# POWER_VOLTAGE.net
KiCad netlist of a schematic drawn in Altium Designer
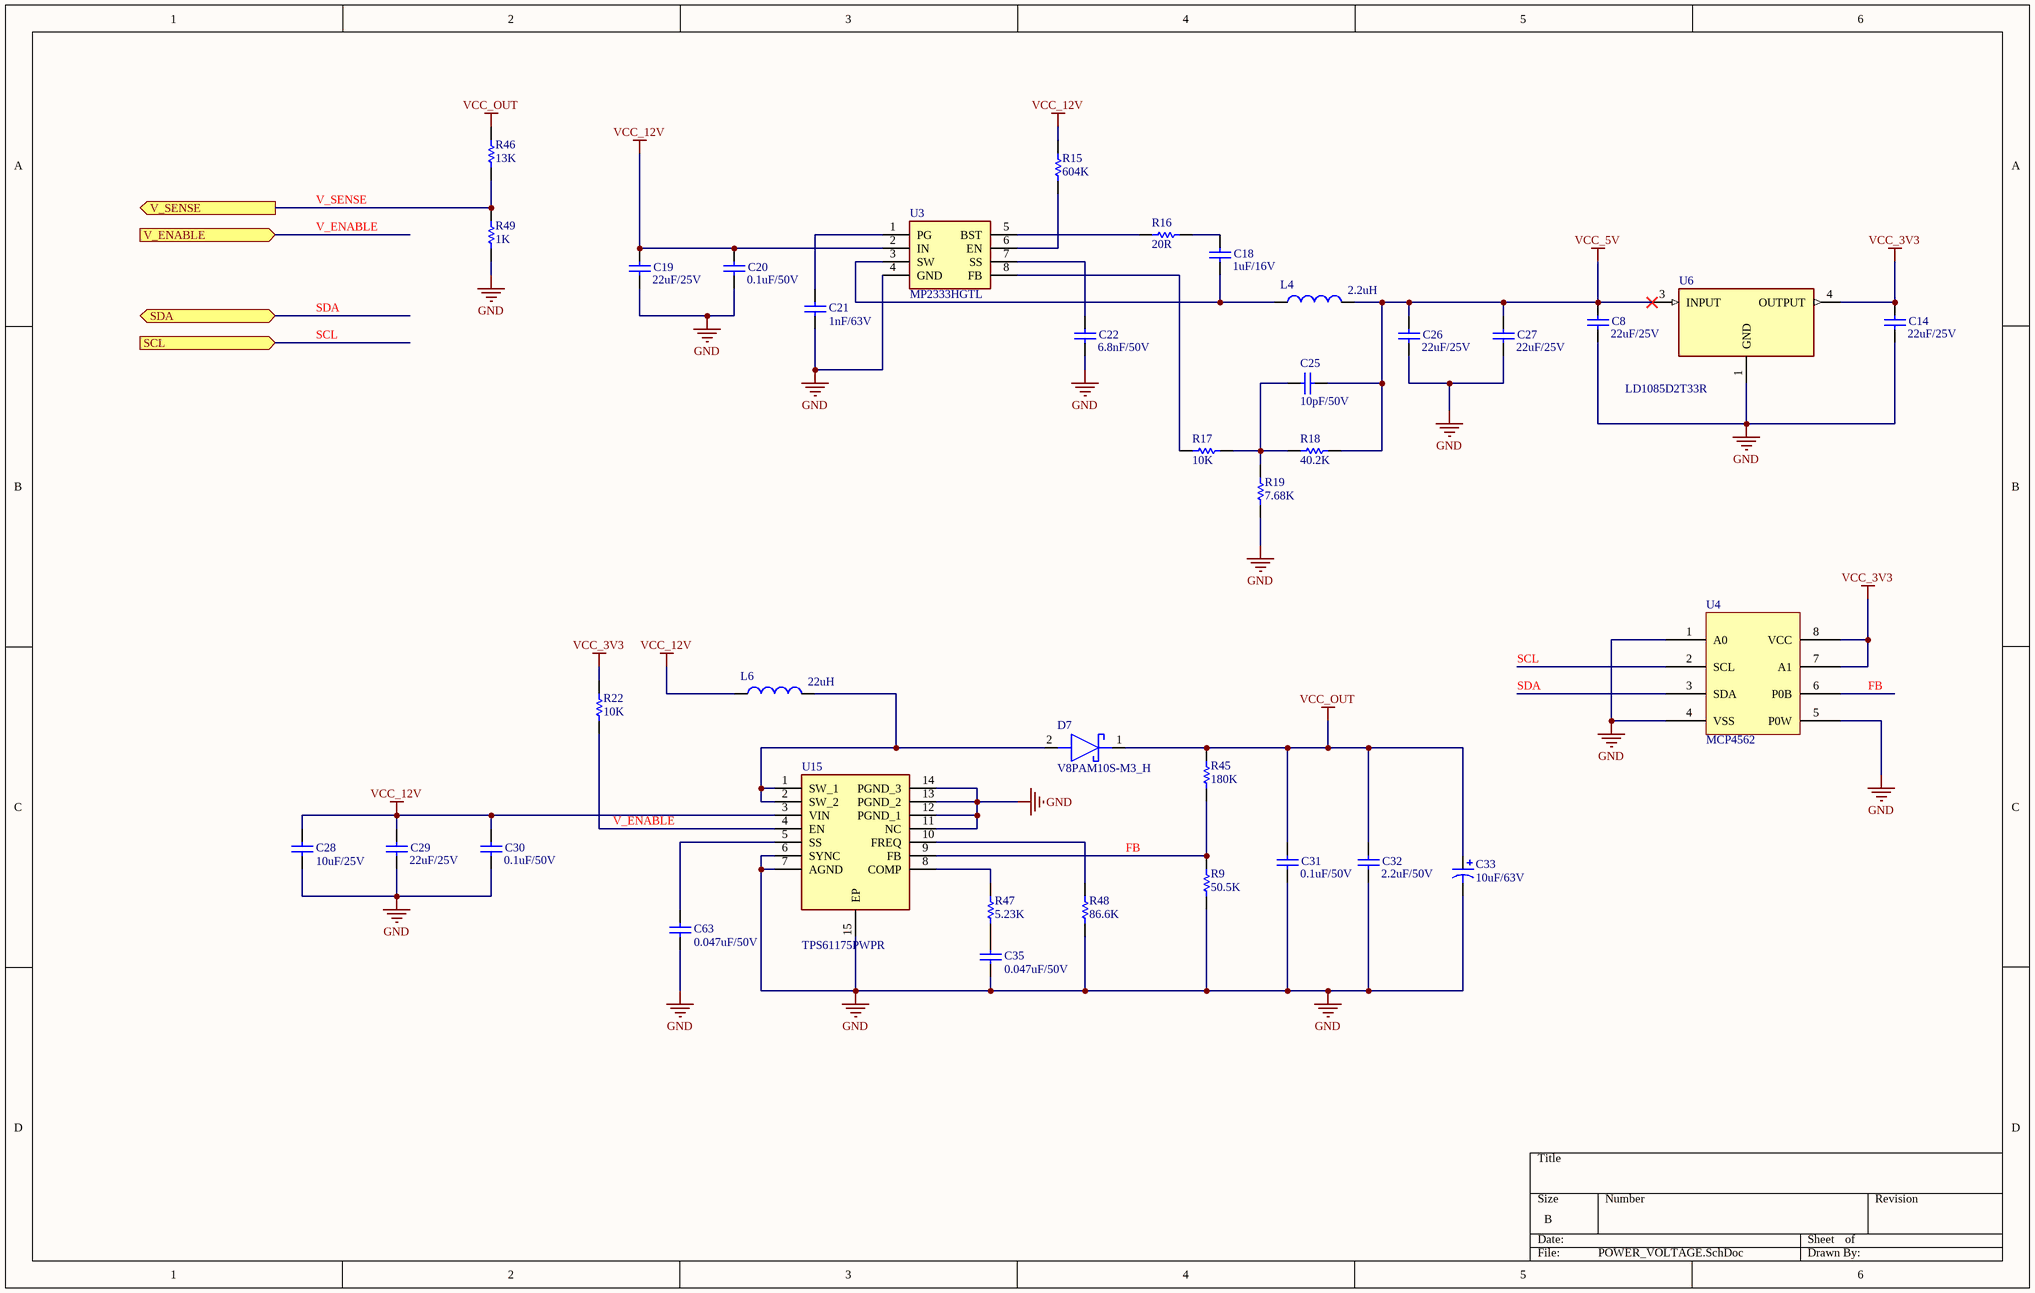
[diagram p0: POWER_VOLTAGE.SchDoc]

(export (version "E")
  (design (tool "Eeschema 10.0.6"))
  (components
    (comp (ref "C8")
      (value "22uF/25V")
      (footprint "1210C")
      (description "Multilayer Ceramic Capacitors MLCC - SMD/SMT 1210 25VDC 22uF 20% X7R AEC-Q200")
      (fields (field (name "MFR") "Taiyo Yuden") (field (name "MFR PART NO") "TMK325B7226MMHP"))
      (libsource (lib "Miscellaneous Devices") (part "Cap"))
    )
    (comp (ref "C14")
      (value "22uF/25V")
      (footprint "1210C")
      (description "Multilayer Ceramic Capacitors MLCC - SMD/SMT 1210 25VDC 22uF 20% X7R AEC-Q200")
      (fields (field (name "MFR") "Taiyo Yuden") (field (name "MFR PART NO") "TMK325B7226MMHP"))
      (libsource (lib "Miscellaneous Devices") (part "Cap"))
    )
    (comp (ref "C18")
      (value "1uF/16V")
      (footprint "0603C")
      (description "Multilayer Ceramic Capacitors MLCC - SMD/SMT 16volts 1uF X7R 10%")
      (fields (field (name "MFR") "KEMET") (field (name "MFR PART NO") "C0603C105K4RAC7411"))
      (libsource (lib "Miscellaneous Devices") (part "Cap"))
    )
    (comp (ref "C19")
      (value "22uF/25V")
      (footprint "1210C")
      (description "Multilayer Ceramic Capacitors MLCC - SMD/SMT 1210 25VDC 22uF 20% X7R AEC-Q200")
      (fields (field (name "MFR") "Taiyo Yuden") (field (name "MFR PART NO") "TMK325B7226MMHP"))
      (libsource (lib "Miscellaneous Devices") (part "Cap"))
    )
    (comp (ref "C20")
      (value "0.1uF/50V")
      (footprint "0603C")
      (description "Multilayer Ceramic Capacitors MLCC - SMD/SMT 50V 0.1uF 0603 X7R 20%")
      (fields (field (name "MFR") "KEMET") (field (name "MFR PART NO") "C0603C104M5RACTU"))
      (libsource (lib "Miscellaneous Devices") (part "Cap"))
    )
    (comp (ref "C21")
      (value "1nF/63V")
      (footprint "0603C")
      (description "Multilayer Ceramic Capacitors MLCC - SMD/SMT 63V 1000pF 0603 X7R 10% AEC-Q200")
      (fields (field (name "MFR") "KEMET") (field (name "MFR PART NO") "80-C0603C102KMREAUTO"))
      (libsource (lib "Miscellaneous Devices") (part "Cap"))
    )
    (comp (ref "C22")
      (value "6.8nF/50V")
      (footprint "0603C")
      (description "Multilayer Ceramic Capacitors MLCC - SMD/SMT 0603 50VDC 6.8nF 5% C0G AEC-Q200")
      (fields (field (name "MFR") "TDK") (field (name "MFR PART NO") "CGA3E2C0G1H682J080AE"))
      (libsource (lib "Miscellaneous Devices") (part "Cap"))
    )
    (comp (ref "C25")
      (value "10pF/50V")
      (footprint "0603C")
      (description "Multilayer Ceramic Capacitors MLCC - SMD/SMT 50V 10pF 0603 C0G 5% AEC-Q200")
      (fields (field (name "MFR") "KEMET") (field (name "MFR PART NO") "C0603C100J5GACAUTO"))
      (libsource (lib "Miscellaneous Devices") (part "Cap"))
    )
    (comp (ref "C26")
      (value "22uF/25V")
      (footprint "1210C")
      (description "Multilayer Ceramic Capacitors MLCC - SMD/SMT 1210 25VDC 22uF 20% X7R AEC-Q200")
      (fields (field (name "MFR") "Taiyo Yuden") (field (name "MFR PART NO") "TMK325B7226MMHP"))
      (libsource (lib "Miscellaneous Devices") (part "Cap"))
    )
    (comp (ref "C27")
      (value "22uF/25V")
      (footprint "1210C")
      (description "Multilayer Ceramic Capacitors MLCC - SMD/SMT 1210 25VDC 22uF 20% X7R AEC-Q200")
      (fields (field (name "MFR") "Taiyo Yuden") (field (name "MFR PART NO") "TMK325B7226MMHP"))
      (libsource (lib "Miscellaneous Devices") (part "Cap"))
    )
    (comp (ref "C28")
      (value "10uF/25V")
      (footprint "0805C")
      (description "Multilayer Ceramic Capacitors MLCC - SMD/SMT 0805 25VDC 10uF 20% X5R")
      (fields (field (name "MFR") "Taiyo Yuden") (field (name "MFR PART NO") "TMK212BBJ106MG-T"))
      (libsource (lib "Miscellaneous Devices") (part "Cap"))
    )
    (comp (ref "C29")
      (value "22uF/25V")
      (footprint "1210C")
      (description "Multilayer Ceramic Capacitors MLCC - SMD/SMT 1210 25VDC 22uF 20% X7R AEC-Q200")
      (fields (field (name "MFR") "Taiyo Yuden") (field (name "MFR PART NO") "TMK325B7226MMHP"))
      (libsource (lib "Miscellaneous Devices") (part "Cap"))
    )
    (comp (ref "C30")
      (value "0.1uF/50V")
      (footprint "0603C")
      (description "Multilayer Ceramic Capacitors MLCC - SMD/SMT 50V 0.1uF 0603 X7R 20%")
      (fields (field (name "MFR") "KEMET") (field (name "MFR PART NO") "C0603C104M5RACTU"))
      (libsource (lib "Miscellaneous Devices") (part "Cap"))
    )
    (comp (ref "C31")
      (value "0.1uF/50V")
      (footprint "0603C")
      (description "Multilayer Ceramic Capacitors MLCC - SMD/SMT 50V 0.1uF 0603 X7R 20%")
      (fields (field (name "MFR") "KEMET") (field (name "MFR PART NO") "C0603C104M5RACTU"))
      (libsource (lib "Miscellaneous Devices") (part "Cap"))
    )
    (comp (ref "C32")
      (value "2.2uF/50V")
      (footprint "0603C")
      (description "Multilayer Ceramic Capacitors MLCC - SMD/SMT 0603 2.2uF 20% 50VDC X5R")
      (fields (field (name "MFR") "Murata Electronics") (field (name "MFR PART NO") "GRM188R61H225ME11J"))
      (libsource (lib "Miscellaneous Devices") (part "Cap"))
    )
    (comp (ref "C33")
      (value "10uF/63V")
      (footprint "EEE-FN1J100L")
      (description "Polarized Capacitor (Radial)")
      (fields (field (name "MFR") "Panasonic") (field (name "MFR PART NO") "EEE-FN1J100L"))
      (libsource (lib "Miscellaneous Devices") (part "Cap Pol1"))
    )
    (comp (ref "C35")
      (value "0.047uF/50V")
      (footprint "0603C")
      (description "Multilayer Ceramic Capacitors MLCC - SMD/SMT 50V 0.047uF 0603 X7R 10%")
      (fields (field (name "MFR") "KEMET") (field (name "MFR PART NO") "C0603C473K5RAC7411"))
      (libsource (lib "Miscellaneous Devices") (part "Cap"))
    )
    (comp (ref "C63")
      (value "0.047uF/50V")
      (footprint "0603C")
      (description "Multilayer Ceramic Capacitors MLCC - SMD/SMT 50V 0.047uF 0603 X7R 10%")
      (fields (field (name "MFR") "KEMET") (field (name "MFR PART NO") "C0603C473K5RAC7411"))
      (libsource (lib "Miscellaneous Devices") (part "Cap"))
    )
    (comp (ref "D7")
      (value "V8PAM10S-M3_H")
      (footprint "V8PAM10SHM3H")
      (description "Schottky Diodes & Rectifiers 8A 100V")
      (fields
        (field (name "MFR") "Vishay General Semiconductor")
        (field (name "MFR PART NO") "V8PAM10S-M3/H")
      )
      (libsource (lib "*") (part "V8PAM10S-M3_H"))
    )
    (comp (ref "L4")
      (value "2.2uH")
      (footprint "IHLP1616BZER2R2M5A")
      (description "Fixed Inductors 2.2uH 20% High Temp AEC-Q200")
      (fields (field (name "MFR") "Vishay / Dale") (field (name "MFR PART NO") "IHLP1616BZER2R2M5A"))
      (libsource (lib "de20") (part "INDUCTOR"))
    )
    (comp (ref "L6")
      (value "22uH")
      (footprint "CDRH124NP-220MC")
      (description "Fixed Inductors 22uH 2.9A 20% SMD PWR INDUCTOR")
      (fields (field (name "MFR") "Sumida") (field (name "MFR PART NO") "CDRH124NP-220MC"))
      (libsource (lib "de20") (part "INDUCTOR"))
    )
    (comp (ref "R9")
      (value "50.5K")
      (footprint "0603R")
      (description "Thin Film Resistors - SMD 50.5kOhm,0603,0.1%,2 5ppm,63mW,50V")
      (fields (field (name "MFR") "KOA Speer") (field (name "MFR PART NO") "RN731JTTD5052B25"))
      (libsource (lib "Miscellaneous Devices") (part "Res1"))
    )
    (comp (ref "R15")
      (value "604K")
      (footprint "0603R")
      (description "Thick Film Resistors - SMD 0603 1% 604Kohm Anti-Sulfur AEC-Q200")
      (fields (field (name "MFR") "Panasonic") (field (name "MFR PART NO") "ERJ-U03F6043V"))
      (libsource (lib "Miscellaneous Devices") (part "Res1"))
    )
    (comp (ref "R16")
      (value "20R")
      (footprint "0603R")
      (description "Thick Film Resistors - SMD 0603 0.25W 1% 20ohm AEC-Q200")
      (fields (field (name "MFR") "Panasonic") (field (name "MFR PART NO") "ERJ-UP3F20R0V"))
      (libsource (lib "Miscellaneous Devices") (part "Res1"))
    )
    (comp (ref "R17")
      (value "10K")
      (footprint "0603R")
      (description "Thick Film Resistors - SMD 0603 10Kohms 1% Anti-Sulfur AEC-Q200")
      (fields (field (name "MFR") "ROHM Semiconductor") (field (name "MFR PART NO") "SFR03EZPF1002"))
      (libsource (lib "Miscellaneous Devices") (part "Res1"))
    )
    (comp (ref "R18")
      (value "40.2K")
      (footprint "0603R")
      (description "Thick Film Resistors - SMD 0603 Anti-Surge Res. 0.1%, 40.2Koh")
      (fields (field (name "MFR") "Panasonic") (field (name "MFR PART NO") "ERJ-PB3B4022V"))
      (libsource (lib "Miscellaneous Devices") (part "Res1"))
    )
    (comp (ref "R19")
      (value "7.68K")
      (footprint "0603R")
      (description "Thick Film Resistors - SMD 0603 Anti-Surge Res. 0.1%, 7.68Koh")
      (fields (field (name "MFR") "Panasonic") (field (name "MFR PART NO") "ERJ-PB3B7681V"))
      (libsource (lib "Miscellaneous Devices") (part "Res1"))
    )
    (comp (ref "R22")
      (value "10K")
      (footprint "0603R")
      (description "Thick Film Resistors - SMD 0603 10Kohms 1% Anti-Sulfur AEC-Q200")
      (fields (field (name "MFR") "ROHM Semiconductor") (field (name "MFR PART NO") "SFR03EZPF1002"))
      (libsource (lib "Miscellaneous Devices") (part "Res1"))
    )
    (comp (ref "R45")
      (value "180K")
      (footprint "0603R")
      (description "Thin Film Resistors - SMD 180K ohm 0.1% 50 ppm")
      (fields (field (name "MFR") "KOA Speer") (field (name "MFR PART NO") "RN73R1JTTD1803B50"))
      (libsource (lib "Miscellaneous Devices") (part "Res1"))
    )
    (comp (ref "R46")
      (value "13K")
      (footprint "0603R")
      (description "Thin Film Resistors - SMD 13K ohm 0.1% 25 ppm")
      (fields (field (name "MFR") "KOA Speer") (field (name "MFR PART NO") "RN73R1JTTD1302B25"))
      (libsource (lib "Miscellaneous Devices") (part "Res1"))
    )
    (comp (ref "R47")
      (value "5.23K")
      (footprint "0603R")
      (description "Thick Film Resistors - SMD 0603 5.23Kohms 1% AEC-Q200")
      (fields (field (name "MFR") "Panasonic") (field (name "MFR PART NO") "ERJ-3EKF5231V"))
      (libsource (lib "Miscellaneous Devices") (part "Res1"))
    )
    (comp (ref "R48")
      (value "86.6K")
      (footprint "0603R")
      (description "Thick Film Resistors - SMD 0603 86.6Kohms 1% AEC-Q200")
      (fields (field (name "MFR") "Panasonic") (field (name "MFR PART NO") "ERJ-3EKF8662V"))
      (libsource (lib "Miscellaneous Devices") (part "Res1"))
    )
    (comp (ref "R49")
      (value "1K")
      (footprint "0603R")
      (description "Resistor")
      (fields (field (name "MFR") "Vishay / Dale") (field (name "MFR PART NO") "CRCW06031K00FKEAC"))
      (libsource (lib "Miscellaneous Devices") (part "Res1"))
    )
    (comp (ref "U3")
      (value "MP2333HGTL")
      (footprint "MP2333HGTL-P")
      (description "Switching Voltage Regulators High-Efficiency, 3A, 18V, 1200kHz, Synchronous, Step-Down Converter")
      (fields
        (field (name "MFR") "Monolithic Power Systems (MPS)")
        (field (name "MFR PART NO") "MP2333HGTL-P")
      )
      (libsource (lib "*") (part "MP2333HGTL"))
    )
    (comp (ref "U4")
      (value "MCP4562")
      (footprint "MCP4562T-503E/MS")
      (description "Digital Potentiometer ICs Sngl 8B NV I2C Rheo")
      (fields (field (name "MFR") "Microchip Technology") (field (name "MFR PART NO") "MCP4562T-503E/MS"))
      (libsource (lib "Schlib1") (part "MCP4562"))
    )
    (comp (ref "U6")
      (value "LD1085D2T33R")
      (footprint "LD1085D2T33R")
      (description "Integrated Circuit")
      (fields
        (field (name "MFR") "STMicroelectronics")
        (field (name "STOCKIEST PART NO") "511-LD1085D2T33-TR")
      )
      (libsource (lib "*") (part "LD1085D2T33R"))
    )
    (comp (ref "U15")
      (value "TPS61175PWPR")
      (footprint "TPS61175PWPR")
      (description "Switching Voltage Regulators 3A High Vltg Boost Converter")
      (fields (field (name "MFR") "Texas Instruments") (field (name "STOCKIEST PART NO") "595-TPS61175PWPR"))
      (libsource (lib "*") (part "TPS61175PWP"))
    )
  )
  (nets
    (net (code "1") (name "/FB") (class "Default")
      (node (ref "R45") (pin "2") (pinfunction "2_2") (pintype "passive"))
      (node (ref "R9") (pin "1") (pinfunction "1_1") (pintype "passive"))
      (node (ref "U15") (pin "9") (pinfunction "FB_9") (pintype "passive"))
      (node (ref "U4") (pin "6") (pinfunction "P0B_6") (pintype "passive"))
    )
    (net (code "2") (name "/SCL") (class "Default")
      (node (ref "U4") (pin "2") (pinfunction "SCL_2") (pintype "passive"))
    )
    (net (code "3") (name "/SDA") (class "Default")
      (node (ref "U4") (pin "3") (pinfunction "SDA_3") (pintype "passive"))
    )
    (net (code "4") (name "/V_ENABLE") (class "Default")
      (node (ref "R22") (pin "2") (pinfunction "2_2") (pintype "passive"))
      (node (ref "U15") (pin "4") (pinfunction "EN_4") (pintype "passive"))
    )
    (net (code "5") (name "/V_SENSE") (class "Default")
      (node (ref "R46") (pin "2") (pinfunction "2_2") (pintype "passive"))
      (node (ref "R49") (pin "2") (pinfunction "2_2") (pintype "passive"))
    )
    (net (code "6") (name "GND") (class "Default")
      (node (ref "C14") (pin "1") (pinfunction "1_1") (pintype "passive"))
      (node (ref "C19") (pin "1") (pinfunction "1_1") (pintype "passive"))
      (node (ref "C20") (pin "1") (pinfunction "1_1") (pintype "passive"))
      (node (ref "C21") (pin "1") (pinfunction "1_1") (pintype "passive"))
      (node (ref "C22") (pin "1") (pinfunction "1_1") (pintype "passive"))
      (node (ref "C26") (pin "1") (pinfunction "1_1") (pintype "passive"))
      (node (ref "C27") (pin "1") (pinfunction "1_1") (pintype "passive"))
      (node (ref "C28") (pin "1") (pinfunction "1_1") (pintype "passive"))
      (node (ref "C29") (pin "1") (pinfunction "1_1") (pintype "passive"))
      (node (ref "C30") (pin "1") (pinfunction "1_1") (pintype "passive"))
      (node (ref "C31") (pin "1") (pinfunction "1_1") (pintype "passive"))
      (node (ref "C32") (pin "1") (pinfunction "1_1") (pintype "passive"))
      (node (ref "C33") (pin "2") (pinfunction "2_2") (pintype "passive"))
      (node (ref "C35") (pin "1") (pinfunction "1_1") (pintype "passive"))
      (node (ref "C63") (pin "1") (pinfunction "1_1") (pintype "passive"))
      (node (ref "C8") (pin "1") (pinfunction "1_1") (pintype "passive"))
      (node (ref "R19") (pin "2") (pinfunction "2_2") (pintype "passive"))
      (node (ref "R48") (pin "1") (pinfunction "1_1") (pintype "passive"))
      (node (ref "R49") (pin "1") (pinfunction "1_1") (pintype "passive"))
      (node (ref "R9") (pin "2") (pinfunction "2_2") (pintype "passive"))
      (node (ref "U15") (pin "11") (pinfunction "NC_11") (pintype "passive"))
      (node (ref "U15") (pin "12") (pinfunction "PGND_1_12") (pintype "passive"))
      (node (ref "U15") (pin "13") (pinfunction "PGND_2_13") (pintype "passive"))
      (node (ref "U15") (pin "14") (pinfunction "PGND_3_14") (pintype "passive"))
      (node (ref "U15") (pin "15") (pinfunction "EP_15") (pintype "passive"))
      (node (ref "U15") (pin "6") (pinfunction "SYNC_6") (pintype "passive"))
      (node (ref "U15") (pin "7") (pinfunction "AGND_7") (pintype "passive"))
      (node (ref "U3") (pin "4") (pinfunction "GND_4") (pintype "passive"))
      (node (ref "U4") (pin "1") (pinfunction "A0_1") (pintype "passive"))
      (node (ref "U4") (pin "4") (pinfunction "VSS_4") (pintype "passive"))
      (node (ref "U4") (pin "5") (pinfunction "P0W_5") (pintype "passive"))
      (node (ref "U6") (pin "1") (pinfunction "GND_1") (pintype "power_in"))
    )
    (net (code "7") (name "Net-(C18-Pad2)") (class "Default")
      (node (ref "C18") (pin "2") (pinfunction "2_2") (pintype "passive"))
      (node (ref "R16") (pin "2") (pinfunction "2_2") (pintype "passive"))
    )
    (net (code "8") (name "Net-(C25-Pad2)") (class "Default")
      (node (ref "C25") (pin "2") (pinfunction "2_2") (pintype "passive"))
      (node (ref "R17") (pin "1") (pinfunction "1_1") (pintype "passive"))
      (node (ref "R18") (pin "1") (pinfunction "1_1") (pintype "passive"))
      (node (ref "R19") (pin "1") (pinfunction "1_1") (pintype "passive"))
    )
    (net (code "9") (name "Net-(C35-Pad2)") (class "Default")
      (node (ref "C35") (pin "2") (pinfunction "2_2") (pintype "passive"))
      (node (ref "R47") (pin "1") (pinfunction "1_1") (pintype "passive"))
    )
    (net (code "10") (name "Net-(D7-A)") (class "Default")
      (node (ref "D7") (pin "2") (pinfunction "A_2") (pintype "passive"))
      (node (ref "L6") (pin "2") (pinfunction "2_2") (pintype "passive"))
      (node (ref "U15") (pin "1") (pinfunction "SW_1_1") (pintype "passive"))
      (node (ref "U15") (pin "2") (pinfunction "SW_2_2") (pintype "passive"))
    )
    (net (code "11") (name "Net-(U3-BST)") (class "Default")
      (node (ref "R16") (pin "1") (pinfunction "1_1") (pintype "passive"))
      (node (ref "U3") (pin "5") (pinfunction "BST_5") (pintype "passive"))
    )
    (net (code "12") (name "Net-(U3-EN)") (class "Default")
      (node (ref "R15") (pin "1") (pinfunction "1_1") (pintype "passive"))
      (node (ref "U3") (pin "6") (pinfunction "EN_6") (pintype "passive"))
    )
    (net (code "13") (name "Net-(U3-FB)") (class "Default")
      (node (ref "R17") (pin "2") (pinfunction "2_2") (pintype "passive"))
      (node (ref "U3") (pin "8") (pinfunction "FB_8") (pintype "passive"))
    )
    (net (code "14") (name "Net-(U3-PG)") (class "Default")
      (node (ref "C21") (pin "2") (pinfunction "2_2") (pintype "passive"))
      (node (ref "U3") (pin "1") (pinfunction "PG_1") (pintype "passive"))
    )
    (net (code "15") (name "Net-(U3-SS)") (class "Default")
      (node (ref "C22") (pin "2") (pinfunction "2_2") (pintype "passive"))
      (node (ref "U3") (pin "7") (pinfunction "SS_7") (pintype "passive"))
    )
    (net (code "16") (name "Net-(U3-SW)") (class "Default")
      (node (ref "C18") (pin "1") (pinfunction "1_1") (pintype "passive"))
      (node (ref "L4") (pin "1") (pinfunction "1_1") (pintype "passive"))
      (node (ref "U3") (pin "3") (pinfunction "SW_3") (pintype "passive"))
    )
    (net (code "17") (name "Net-(U15-COMP)") (class "Default")
      (node (ref "R47") (pin "2") (pinfunction "2_2") (pintype "passive"))
      (node (ref "U15") (pin "8") (pinfunction "COMP_8") (pintype "passive"))
    )
    (net (code "18") (name "Net-(U15-FREQ)") (class "Default")
      (node (ref "R48") (pin "2") (pinfunction "2_2") (pintype "passive"))
      (node (ref "U15") (pin "10") (pinfunction "FREQ_10") (pintype "passive"))
    )
    (net (code "19") (name "Net-(U15-SS)") (class "Default")
      (node (ref "C63") (pin "2") (pinfunction "2_2") (pintype "passive"))
      (node (ref "U15") (pin "5") (pinfunction "SS_5") (pintype "passive"))
    )
    (net (code "20") (name "VCC_3V3") (class "Default")
      (node (ref "C14") (pin "2") (pinfunction "2_2") (pintype "passive"))
      (node (ref "R22") (pin "1") (pinfunction "1_1") (pintype "passive"))
      (node (ref "U4") (pin "7") (pinfunction "A1_7") (pintype "passive"))
      (node (ref "U4") (pin "8") (pinfunction "VCC_8") (pintype "passive"))
      (node (ref "U6") (pin "4") (pinfunction "OUTPUT_4") (pintype "output"))
    )
    (net (code "21") (name "VCC_5V") (class "Default")
      (node (ref "C25") (pin "1") (pinfunction "1_1") (pintype "passive"))
      (node (ref "C26") (pin "2") (pinfunction "2_2") (pintype "passive"))
      (node (ref "C27") (pin "2") (pinfunction "2_2") (pintype "passive"))
      (node (ref "C8") (pin "2") (pinfunction "2_2") (pintype "passive"))
      (node (ref "L4") (pin "2") (pinfunction "2_2") (pintype "passive"))
      (node (ref "R18") (pin "2") (pinfunction "2_2") (pintype "passive"))
      (node (ref "U6") (pin "3") (pinfunction "INPUT_3") (pintype "input"))
    )
    (net (code "22") (name "VCC_12V") (class "Default")
      (node (ref "C19") (pin "2") (pinfunction "2_2") (pintype "passive"))
      (node (ref "C20") (pin "2") (pinfunction "2_2") (pintype "passive"))
      (node (ref "C28") (pin "2") (pinfunction "2_2") (pintype "passive"))
      (node (ref "C29") (pin "2") (pinfunction "2_2") (pintype "passive"))
      (node (ref "C30") (pin "2") (pinfunction "2_2") (pintype "passive"))
      (node (ref "L6") (pin "1") (pinfunction "1_1") (pintype "passive"))
      (node (ref "R15") (pin "2") (pinfunction "2_2") (pintype "passive"))
      (node (ref "U15") (pin "3") (pinfunction "VIN_3") (pintype "passive"))
      (node (ref "U3") (pin "2") (pinfunction "IN_2") (pintype "passive"))
    )
    (net (code "23") (name "VCC_OUT") (class "Default")
      (node (ref "C31") (pin "2") (pinfunction "2_2") (pintype "passive"))
      (node (ref "C32") (pin "2") (pinfunction "2_2") (pintype "passive"))
      (node (ref "C33") (pin "1") (pinfunction "1_1") (pintype "passive"))
      (node (ref "D7") (pin "1") (pinfunction "K_1") (pintype "passive"))
      (node (ref "R45") (pin "1") (pinfunction "1_1") (pintype "passive"))
      (node (ref "R46") (pin "1") (pinfunction "1_1") (pintype "passive"))
    )
  )
)
